# Sheet1.net
KiCad netlist of a schematic drawn in Altium Designer
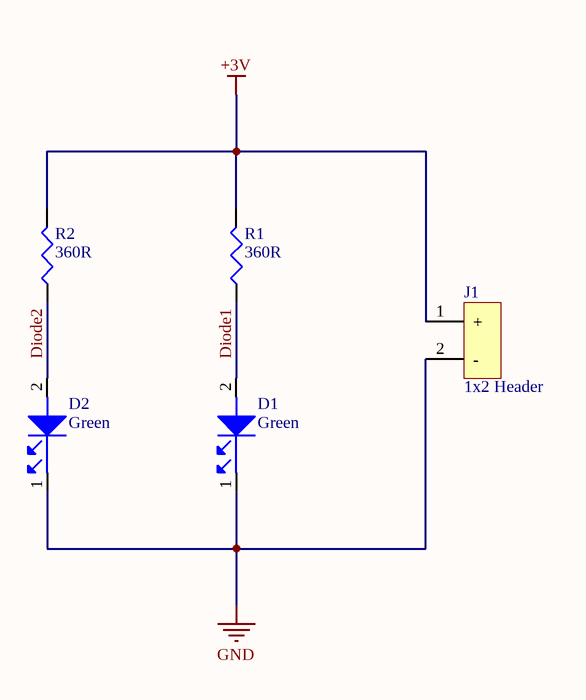
[diagram p0: Sheet1.SchDoc]

(export (version "E")
  (design (tool "Eeschema 10.0.6"))
  (components
    (comp (ref "D1")
      (value "Green")
      (footprint "Resistor")
      (description "LED Uni-Color Green 574nm 2-Pin Chip LED T/R")
      (fields
        (field (name "MANUFACTURER") "Vishay Lite-On")
        (field (name "MANUFACTURER PART NUMBER") "LTST-C191KGKT")
      )
      (libsource (lib "Schlib1") (part "LTST-C191KGKT"))
    )
    (comp (ref "D2")
      (value "Green")
      (footprint "Resistor")
      (description "LED Uni-Color Green 574nm 2-Pin Chip LED T/R")
      (fields
        (field (name "MANUFACTURER") "Vishay Lite-On")
        (field (name "MANUFACTURER PART NUMBER") "LTST-C191KGKT")
      )
      (libsource (lib "Schlib1") (part "LTST-C191KGKT"))
    )
    (comp (ref "J1")
      (value "1x2 Header")
      (footprint "header 1x2")
      (description "MOLEX - 22-27-2021 - WIRE-BOARD CONNECTOR HEADER 2 POSITION, 2.54MM")
      (fields (field (name "MANUFACTURER") "Molex") (field (name "MANUFACTURER PART NUMBER") "22-27-2021"))
      (libsource (lib "Schlib1") (part "22-27-2021"))
    )
    (comp (ref "R1")
      (value "360R")
      (footprint "Resistor - duplicate")
      (description "RES SMD 360 OHM 1% 1/2W 0805")
      (fields
        (field (name "MANUFACTURER") "Vishay Dale")
        (field (name "MANUFACTURER PART NUMBER") "CRCW0805360RFKEAHP")
      )
      (libsource (lib "Schlib1") (part "CRCW0805360RFKEAHP"))
    )
    (comp (ref "R2")
      (value "360R")
      (footprint "Resistor - duplicate")
      (description "RES SMD 360 OHM 1% 1/2W 0805")
      (fields
        (field (name "MANUFACTURER") "Vishay Dale")
        (field (name "MANUFACTURER PART NUMBER") "CRCW0805360RFKEAHP")
      )
      (libsource (lib "Schlib1") (part "CRCW0805360RFKEAHP"))
    )
  )
  (nets
    (net (code "1") (name "+3V") (class "Default")
      (node (ref "J1") (pin "1") (pinfunction "+_1") (pintype "passive"))
      (node (ref "R1") (pin "2") (pinfunction "2_2") (pintype "passive"))
      (node (ref "R2") (pin "2") (pinfunction "2_2") (pintype "passive"))
    )
    (net (code "2") (name "/Diode1") (class "Default")
      (node (ref "D1") (pin "2") (pinfunction "2_2") (pintype "passive"))
      (node (ref "R1") (pin "1") (pinfunction "1_1") (pintype "passive"))
    )
    (net (code "3") (name "/Diode2") (class "Default")
      (node (ref "D2") (pin "2") (pinfunction "2_2") (pintype "passive"))
      (node (ref "R2") (pin "1") (pinfunction "1_1") (pintype "passive"))
    )
    (net (code "4") (name "GND") (class "Default")
      (node (ref "D1") (pin "1") (pinfunction "1_1") (pintype "passive"))
      (node (ref "D2") (pin "1") (pinfunction "1_1") (pintype "passive"))
      (node (ref "J1") (pin "2") (pinfunction "-_2") (pintype "passive"))
    )
  )
)
